# Power_CH341A.net
KiCad netlist of a schematic drawn in Altium Designer
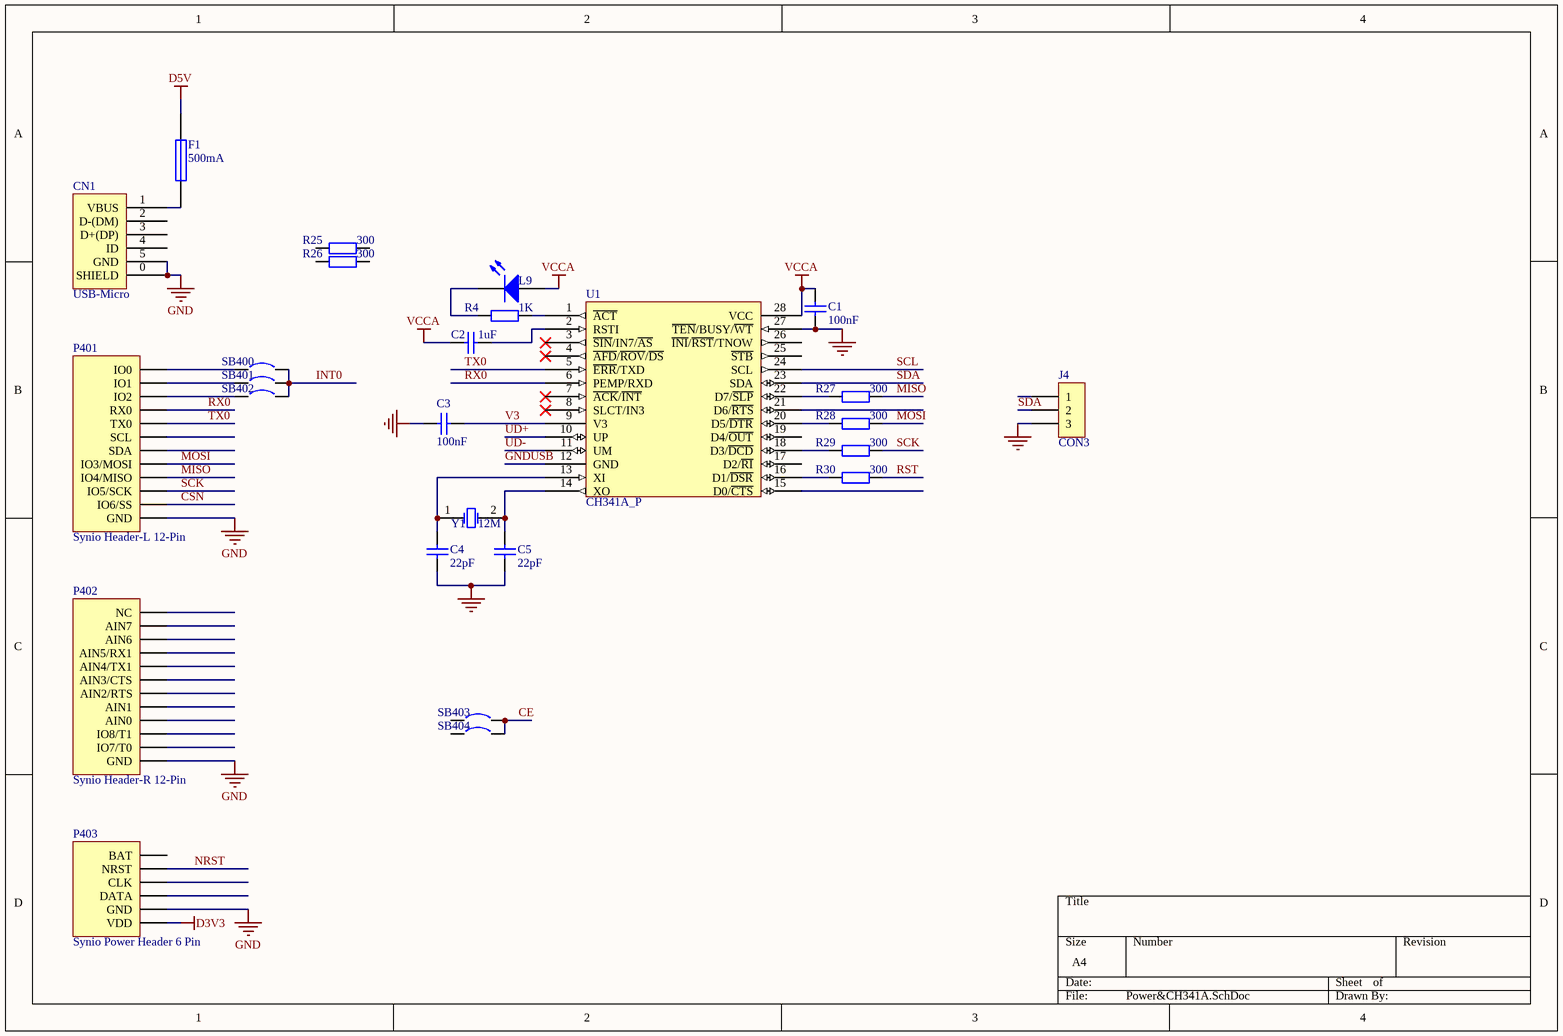
[diagram p0: Power&CH341A.SchDoc]

(export (version "E")
  (design (tool "Eeschema 10.0.6"))
  (components
    (comp (ref "C1")
      (value "100nF")
      (footprint "C0603L")
      (description "Capacitor")
      (fields (field (name "Comment") "Cap") (field (name "PUBLISHER") "Altium Limited"))
      (libsource (lib "Miscellaneous Devices") (part "Cap"))
    )
    (comp (ref "C2")
      (value "1uF")
      (footprint "C0603L")
      (description "Capacitor")
      (fields (field (name "Comment") "Cap") (field (name "PUBLISHER") "Altium Limited"))
      (libsource (lib "Miscellaneous Devices") (part "Cap"))
    )
    (comp (ref "C3")
      (value "100nF")
      (footprint "C0603L")
      (description "Capacitor")
      (fields (field (name "Comment") "Cap") (field (name "PUBLISHER") "Altium Limited"))
      (libsource (lib "Miscellaneous Devices") (part "Cap"))
    )
    (comp (ref "C4")
      (value "22pF")
      (footprint "C0603L")
      (description "Capacitor")
      (fields (field (name "Comment") "Cap") (field (name "PUBLISHER") "Altium Limited"))
      (libsource (lib "Miscellaneous Devices") (part "Cap"))
    )
    (comp (ref "C5")
      (value "22pF")
      (footprint "C0603L")
      (description "Capacitor")
      (fields (field (name "Comment") "Cap") (field (name "PUBLISHER") "Altium Limited"))
      (libsource (lib "Miscellaneous Devices") (part "Cap"))
    )
    (comp (ref "CN1")
      (value "USB-Micro")
      (footprint "USB-MICRO-Female-Lite")
      (libsource (lib "Connector") (part "USB-Micro"))
    )
    (comp (ref "F1")
      (value "500mA")
      (footprint "0805")
      (description "Fuse")
      (fields (field (name "PUBLISHER") "Altium Limited"))
      (libsource (lib "Studio") (part "Fuse 1"))
    )
    (comp (ref "J4")
      (value "CON3")
      (footprint "HDR1X3")
      (description "CON 3-Pin")
      (fields (field (name "PUBLISHER") "Altium Limited"))
      (libsource (lib "CT107D_SUDA") (part "CON3"))
    )
    (comp (ref "L9")
      (value "LED")
      (footprint "0603pn")
      (description "Typical RED, GREEN, YELLOW, AMBER GaAs LED")
      (fields (field (name "PUBLISHER") "Altium Limited"))
      (libsource (lib "CT107D_SUDA") (part "LED"))
    )
    (comp (ref "P401")
      (value "Synio Header-L 12-Pin")
      (footprint "HDR1X12-L/2.54MM")
      (description "Synio Header-L, 12-Pin")
      (fields (field (name "PUBLISHER") "Altium Limited"))
      (libsource (lib "Connector") (part "Synio Header-L 12-Pin"))
    )
    (comp (ref "P402")
      (value "Synio Header-R 12-Pin")
      (footprint "HDR1X12-L/2.54MM")
      (description "Synio Header-R, 12-Pin")
      (fields (field (name "PUBLISHER") "Altium Limited"))
      (libsource (lib "Connector") (part "Synio Header-R 12-Pin"))
    )
    (comp (ref "P403")
      (value "Synio Power Header 6 Pin")
      (footprint "HDR1X6-L/2.54MM")
      (libsource (lib "Connector") (part "Synio Power Header 6 Pin"))
    )
    (comp (ref "R4")
      (value "1K")
      (footprint "R0603")
      (description "Resistor")
      (fields (field (name "Comment") "Res") (field (name "PUBLISHER") "Altium Limited"))
      (libsource (lib "CT107D_SUDA") (part "Res"))
    )
    (comp (ref "R25")
      (value "300")
      (footprint "R0603")
      (description "Resistor")
      (fields (field (name "Comment") "Res") (field (name "PUBLISHER") "Altium Limited"))
      (libsource (lib "CT107D_SUDA") (part "Res"))
    )
    (comp (ref "R26")
      (value "300")
      (footprint "R0603")
      (description "Resistor")
      (fields (field (name "Comment") "Res") (field (name "PUBLISHER") "Altium Limited"))
      (libsource (lib "CT107D_SUDA") (part "Res"))
    )
    (comp (ref "R27")
      (value "300")
      (footprint "R0603")
      (description "Resistor")
      (fields (field (name "Comment") "Res") (field (name "PUBLISHER") "Altium Limited"))
      (libsource (lib "CT107D_SUDA") (part "Res"))
    )
    (comp (ref "R28")
      (value "300")
      (footprint "R0603")
      (description "Resistor")
      (fields (field (name "Comment") "Res") (field (name "PUBLISHER") "Altium Limited"))
      (libsource (lib "CT107D_SUDA") (part "Res"))
    )
    (comp (ref "R29")
      (value "300")
      (footprint "R0603")
      (description "Resistor")
      (fields (field (name "Comment") "Res") (field (name "PUBLISHER") "Altium Limited"))
      (libsource (lib "CT107D_SUDA") (part "Res"))
    )
    (comp (ref "R30")
      (value "300")
      (footprint "R0603")
      (description "Resistor")
      (fields (field (name "Comment") "Res") (field (name "PUBLISHER") "Altium Limited"))
      (libsource (lib "CT107D_SUDA") (part "Res"))
    )
    (comp (ref "SB400")
      (value "Circuit Breaker")
      (footprint "JP2_SMD")
      (fields (field (name "PUBLISHER") "Altium Limited"))
      (libsource (lib "Misc") (part "Circuit Breaker"))
    )
    (comp (ref "SB401")
      (value "Circuit Breaker")
      (footprint "JP2_SMD")
      (fields (field (name "PUBLISHER") "Altium Limited"))
      (libsource (lib "Misc") (part "Circuit Breaker"))
    )
    (comp (ref "SB402")
      (value "Circuit Breaker")
      (footprint "JP2_SMD")
      (fields (field (name "PUBLISHER") "Altium Limited"))
      (libsource (lib "Misc") (part "Circuit Breaker"))
    )
    (comp (ref "SB403")
      (value "Circuit Breaker")
      (footprint "JP2_SMD")
      (fields (field (name "PUBLISHER") "Altium Limited"))
      (libsource (lib "Misc") (part "Circuit Breaker"))
    )
    (comp (ref "SB404")
      (value "Circuit Breaker")
      (footprint "JP2_SMD")
      (fields (field (name "PUBLISHER") "Altium Limited"))
      (libsource (lib "Misc") (part "Circuit Breaker"))
    )
    (comp (ref "U1")
      (value "CH341A_P")
      (footprint "SO28_M")
      (description "USB bus convert chip")
      (libsource (lib "Logic") (part "CH341A"))
    )
    (comp (ref "Y1")
      (value "12M")
      (footprint "XTAL_49S")
      (description "Crystal Oscillator")
      (fields (field (name "Comment") "XTAL") (field (name "PUBLISHER") "Altium Limited"))
      (libsource (lib "CT107D_SUDA") (part "XTAL"))
    )
  )
  (nets
    (net (code "1") (name "/CE") (class "Default")
      (node (ref "SB403") (pin "2") (pinfunction "2_2") (pintype "passive"))
      (node (ref "SB404") (pin "2") (pinfunction "2_2") (pintype "passive"))
    )
    (net (code "2") (name "/CSN") (class "Default")
      (node (ref "P401") (pin "2") (pinfunction "IO6/SS_2") (pintype "passive"))
    )
    (net (code "3") (name "/INT0") (class "Default")
      (node (ref "SB400") (pin "2") (pinfunction "2_2") (pintype "passive"))
      (node (ref "SB401") (pin "2") (pinfunction "2_2") (pintype "passive"))
      (node (ref "SB402") (pin "2") (pinfunction "2_2") (pintype "passive"))
    )
    (net (code "4") (name "/MISO") (class "Default")
      (node (ref "P401") (pin "4") (pinfunction "IO4/MISO_4") (pintype "passive"))
      (node (ref "R27") (pin "2") (pinfunction "2_2") (pintype "passive"))
    )
    (net (code "5") (name "/MOSI") (class "Default")
      (node (ref "P401") (pin "5") (pinfunction "IO3/MOSI_5") (pintype "passive"))
      (node (ref "R28") (pin "2") (pinfunction "2_2") (pintype "passive"))
    )
    (net (code "6") (name "/NRST") (class "Default")
      (node (ref "P403") (pin "5") (pinfunction "NRST_5") (pintype "passive"))
    )
    (net (code "7") (name "/RST") (class "Default")
      (node (ref "R30") (pin "2") (pinfunction "2_2") (pintype "passive"))
    )
    (net (code "8") (name "/RX0") (class "Default")
      (node (ref "P401") (pin "9") (pinfunction "RX0_9") (pintype "passive"))
      (node (ref "U1") (pin "6") (pinfunction "PEMP/RXD_6") (pintype "input"))
    )
    (net (code "9") (name "/SCK") (class "Default")
      (node (ref "P401") (pin "3") (pinfunction "IO5/SCK_3") (pintype "passive"))
      (node (ref "R29") (pin "2") (pinfunction "2_2") (pintype "passive"))
    )
    (net (code "10") (name "/SCL") (class "Default")
      (node (ref "U1") (pin "24") (pinfunction "SCL_24") (pintype "output"))
    )
    (net (code "11") (name "/SDA") (class "Default")
      (node (ref "J4") (pin "2") (pinfunction "2_2") (pintype "passive"))
      (node (ref "U1") (pin "23") (pinfunction "SDA_23") (pintype "bidirectional"))
    )
    (net (code "12") (name "/TX0") (class "Default")
      (node (ref "P401") (pin "8") (pinfunction "TX0_8") (pintype "passive"))
      (node (ref "U1") (pin "5") (pinfunction "~{ERR}/TXD_5") (pintype "input"))
    )
    (net (code "13") (name "/UD+") (class "Default")
      (node (ref "U1") (pin "10") (pinfunction "UP_10") (pintype "bidirectional"))
    )
    (net (code "14") (name "/UD-") (class "Default")
      (node (ref "U1") (pin "11") (pinfunction "UM_11") (pintype "bidirectional"))
    )
    (net (code "15") (name "/V3") (class "Default")
      (node (ref "C3") (pin "1") (pinfunction "1_1") (pintype "passive"))
      (node (ref "U1") (pin "9") (pinfunction "V3_9") (pintype "power_in"))
    )
    (net (code "16") (name "D3V3") (class "Default")
      (node (ref "P403") (pin "1") (pinfunction "VDD_1") (pintype "passive"))
    )
    (net (code "17") (name "D5V") (class "Default")
      (node (ref "F1") (pin "1") (pinfunction "1_1") (pintype "passive"))
    )
    (net (code "18") (name "GND") (class "Default")
      (node (ref "CN1") (pin "0") (pinfunction "SHIELD_0") (pintype "passive"))
      (node (ref "CN1") (pin "5") (pinfunction "GND_5") (pintype "passive"))
      (node (ref "P401") (pin "1") (pinfunction "GND_1") (pintype "passive"))
      (node (ref "P402") (pin "1") (pinfunction "GND_1") (pintype "passive"))
      (node (ref "P403") (pin "2") (pinfunction "GND_2") (pintype "passive"))
    )
    (net (code "19") (name "GNDUSB") (class "Default")
      (node (ref "C1") (pin "1") (pinfunction "1_1") (pintype "passive"))
      (node (ref "C3") (pin "2") (pinfunction "2_2") (pintype "passive"))
      (node (ref "C4") (pin "1") (pinfunction "1_1") (pintype "passive"))
      (node (ref "C5") (pin "1") (pinfunction "1_1") (pintype "passive"))
      (node (ref "J4") (pin "3") (pinfunction "3_3") (pintype "passive"))
      (node (ref "U1") (pin "12") (pinfunction "GND_12") (pintype "power_in"))
      (node (ref "U1") (pin "27") (pinfunction "~{TEN}/BUSY/~{WT}_27") (pintype "input"))
    )
    (net (code "20") (name "Net-(CN1-VBUS)") (class "Default")
      (node (ref "CN1") (pin "1") (pinfunction "VBUS_1") (pintype "passive"))
      (node (ref "F1") (pin "2") (pinfunction "2_2") (pintype "passive"))
    )
    (net (code "21") (name "Net-(L9-K)") (class "Default")
      (node (ref "L9") (pin "2") (pinfunction "K_2") (pintype "passive"))
      (node (ref "R4") (pin "1") (pinfunction "1_1") (pintype "passive"))
    )
    (net (code "22") (name "Net-(P401-IO0)") (class "Default")
      (node (ref "P401") (pin "12") (pinfunction "IO0_12") (pintype "passive"))
      (node (ref "SB400") (pin "1") (pinfunction "1_1") (pintype "passive"))
    )
    (net (code "23") (name "Net-(P401-IO1)") (class "Default")
      (node (ref "P401") (pin "11") (pinfunction "IO1_11") (pintype "passive"))
      (node (ref "SB401") (pin "1") (pinfunction "1_1") (pintype "passive"))
    )
    (net (code "24") (name "Net-(P401-IO2)") (class "Default")
      (node (ref "P401") (pin "10") (pinfunction "IO2_10") (pintype "passive"))
      (node (ref "SB402") (pin "1") (pinfunction "1_1") (pintype "passive"))
    )
    (net (code "25") (name "Net-(U1-D1{slash}~{DSR})") (class "Default")
      (node (ref "R30") (pin "1") (pinfunction "1_1") (pintype "passive"))
      (node (ref "U1") (pin "16") (pinfunction "D1/~{DSR}_16") (pintype "bidirectional"))
    )
    (net (code "26") (name "Net-(U1-D3{slash}~{DCD})") (class "Default")
      (node (ref "R29") (pin "1") (pinfunction "1_1") (pintype "passive"))
      (node (ref "U1") (pin "18") (pinfunction "D3/~{DCD}_18") (pintype "bidirectional"))
    )
    (net (code "27") (name "Net-(U1-D5{slash}~{DTR})") (class "Default")
      (node (ref "R28") (pin "1") (pinfunction "1_1") (pintype "passive"))
      (node (ref "U1") (pin "20") (pinfunction "D5/~{DTR}_20") (pintype "bidirectional"))
    )
    (net (code "28") (name "Net-(U1-D7{slash}~{SLP})") (class "Default")
      (node (ref "R27") (pin "1") (pinfunction "1_1") (pintype "passive"))
      (node (ref "U1") (pin "22") (pinfunction "D7/~{SLP}_22") (pintype "bidirectional"))
    )
    (net (code "29") (name "Net-(U1-RSTI)") (class "Default")
      (node (ref "C2") (pin "1") (pinfunction "1_1") (pintype "passive"))
      (node (ref "U1") (pin "2") (pinfunction "RSTI_2") (pintype "input"))
    )
    (net (code "30") (name "Net-(U1-XI)") (class "Default")
      (node (ref "C4") (pin "2") (pinfunction "2_2") (pintype "passive"))
      (node (ref "U1") (pin "13") (pinfunction "XI_13") (pintype "input"))
      (node (ref "Y1") (pin "1") (pinfunction "OSC1_1") (pintype "passive"))
    )
    (net (code "31") (name "Net-(U1-XO)") (class "Default")
      (node (ref "C5") (pin "2") (pinfunction "2_2") (pintype "passive"))
      (node (ref "U1") (pin "14") (pinfunction "XO_14") (pintype "output"))
      (node (ref "Y1") (pin "2") (pinfunction "OSC2_2") (pintype "passive"))
    )
    (net (code "32") (name "Net-(U1-~{ACT})") (class "Default")
      (node (ref "R4") (pin "2") (pinfunction "2_2") (pintype "passive"))
      (node (ref "U1") (pin "1") (pinfunction "~{ACT}_1") (pintype "output"))
    )
    (net (code "33") (name "VCCA") (class "Default")
      (node (ref "C1") (pin "2") (pinfunction "2_2") (pintype "passive"))
      (node (ref "C2") (pin "2") (pinfunction "2_2") (pintype "passive"))
      (node (ref "L9") (pin "1") (pinfunction "A_1") (pintype "passive"))
      (node (ref "U1") (pin "28") (pinfunction "VCC_28") (pintype "power_in"))
    )
    (net (code "34") (name "unconnected-(CN1-D+(DP)-Pad3)") (class "Default")
      (node (ref "CN1") (pin "3") (pinfunction "D+(DP)_3") (pintype "passive"))
    )
    (net (code "35") (name "unconnected-(CN1-D-(DM)-Pad2)") (class "Default")
      (node (ref "CN1") (pin "2") (pinfunction "D-(DM)_2") (pintype "passive"))
    )
    (net (code "36") (name "unconnected-(CN1-ID-Pad4)") (class "Default")
      (node (ref "CN1") (pin "4") (pinfunction "ID_4") (pintype "passive"))
    )
    (net (code "37") (name "unconnected-(J4-Pad1)") (class "Default")
      (node (ref "J4") (pin "1") (pinfunction "1_1") (pintype "passive"))
    )
    (net (code "38") (name "unconnected-(P401-SCL-Pad7)") (class "Default")
      (node (ref "P401") (pin "7") (pinfunction "SCL_7") (pintype "passive"))
    )
    (net (code "39") (name "unconnected-(P401-SDA-Pad6)") (class "Default")
      (node (ref "P401") (pin "6") (pinfunction "SDA_6") (pintype "passive"))
    )
    (net (code "40") (name "unconnected-(P402-AIN0-Pad4)") (class "Default")
      (node (ref "P402") (pin "4") (pinfunction "AIN0_4") (pintype "passive"))
    )
    (net (code "41") (name "unconnected-(P402-AIN1-Pad5)") (class "Default")
      (node (ref "P402") (pin "5") (pinfunction "AIN1_5") (pintype "passive"))
    )
    (net (code "42") (name "unconnected-(P402-AIN2{slash}RTS-Pad6)") (class "Default")
      (node (ref "P402") (pin "6") (pinfunction "AIN2/RTS_6") (pintype "passive"))
    )
    (net (code "43") (name "unconnected-(P402-AIN3{slash}CTS-Pad7)") (class "Default")
      (node (ref "P402") (pin "7") (pinfunction "AIN3/CTS_7") (pintype "passive"))
    )
    (net (code "44") (name "unconnected-(P402-AIN4{slash}TX1-Pad8)") (class "Default")
      (node (ref "P402") (pin "8") (pinfunction "AIN4/TX1_8") (pintype "passive"))
    )
    (net (code "45") (name "unconnected-(P402-AIN5{slash}RX1-Pad9)") (class "Default")
      (node (ref "P402") (pin "9") (pinfunction "AIN5/RX1_9") (pintype "passive"))
    )
    (net (code "46") (name "unconnected-(P402-AIN6-Pad10)") (class "Default")
      (node (ref "P402") (pin "10") (pinfunction "AIN6_10") (pintype "passive"))
    )
    (net (code "47") (name "unconnected-(P402-AIN7-Pad11)") (class "Default")
      (node (ref "P402") (pin "11") (pinfunction "AIN7_11") (pintype "passive"))
    )
    (net (code "48") (name "unconnected-(P402-IO7{slash}T0-Pad2)") (class "Default")
      (node (ref "P402") (pin "2") (pinfunction "IO7/T0_2") (pintype "passive"))
    )
    (net (code "49") (name "unconnected-(P402-IO8{slash}T1-Pad3)") (class "Default")
      (node (ref "P402") (pin "3") (pinfunction "IO8/T1_3") (pintype "passive"))
    )
    (net (code "50") (name "unconnected-(P402-NC-Pad12)") (class "Default")
      (node (ref "P402") (pin "12") (pinfunction "NC_12") (pintype "passive"))
    )
    (net (code "51") (name "unconnected-(P403-BAT-Pad6)") (class "Default")
      (node (ref "P403") (pin "6") (pinfunction "BAT_6") (pintype "passive"))
    )
    (net (code "52") (name "unconnected-(P403-CLK-Pad4)") (class "Default")
      (node (ref "P403") (pin "4") (pinfunction "CLK_4") (pintype "passive"))
    )
    (net (code "53") (name "unconnected-(P403-DATA-Pad3)") (class "Default")
      (node (ref "P403") (pin "3") (pinfunction "DATA_3") (pintype "passive"))
    )
    (net (code "54") (name "unconnected-(R25-Pad1)") (class "Default")
      (node (ref "R25") (pin "1") (pinfunction "1_1") (pintype "passive"))
    )
    (net (code "55") (name "unconnected-(R25-Pad2)") (class "Default")
      (node (ref "R25") (pin "2") (pinfunction "2_2") (pintype "passive"))
    )
    (net (code "56") (name "unconnected-(R26-Pad1)") (class "Default")
      (node (ref "R26") (pin "1") (pinfunction "1_1") (pintype "passive"))
    )
    (net (code "57") (name "unconnected-(R26-Pad2)") (class "Default")
      (node (ref "R26") (pin "2") (pinfunction "2_2") (pintype "passive"))
    )
    (net (code "58") (name "unconnected-(SB403-Pad1)") (class "Default")
      (node (ref "SB403") (pin "1") (pinfunction "1_1") (pintype "passive"))
    )
    (net (code "59") (name "unconnected-(SB404-Pad1)") (class "Default")
      (node (ref "SB404") (pin "1") (pinfunction "1_1") (pintype "passive"))
    )
    (net (code "60") (name "unconnected-(U1-D0{slash}~{CTS}-Pad15)") (class "Default")
      (node (ref "U1") (pin "15") (pinfunction "D0/~{CTS}_15") (pintype "bidirectional"))
    )
    (net (code "61") (name "unconnected-(U1-D2{slash}~{RI}-Pad17)") (class "Default")
      (node (ref "U1") (pin "17") (pinfunction "D2/~{RI}_17") (pintype "bidirectional"))
    )
    (net (code "62") (name "unconnected-(U1-D4{slash}~{OUT}-Pad19)") (class "Default")
      (node (ref "U1") (pin "19") (pinfunction "D4/~{OUT}_19") (pintype "bidirectional"))
    )
    (net (code "63") (name "unconnected-(U1-D6{slash}~{RTS}-Pad21)") (class "Default")
      (node (ref "U1") (pin "21") (pinfunction "D6/~{RTS}_21") (pintype "bidirectional"))
    )
    (net (code "64") (name "unconnected-(U1-SLCT{slash}IN3-Pad8)") (class "Default")
      (node (ref "U1") (pin "8") (pinfunction "SLCT/IN3_8") (pintype "input+no_connect"))
    )
    (net (code "65") (name "unconnected-(U1-~{ACK}{slash}~{INT}-Pad7)") (class "Default")
      (node (ref "U1") (pin "7") (pinfunction "~{ACK}/~{INT}_7") (pintype "input+no_connect"))
    )
    (net (code "66") (name "unconnected-(U1-~{AFD}{slash}~{ROV}{slash}~{DS}-Pad4)") (class "Default")
      (node (ref "U1") (pin "4") (pinfunction "~{AFD}/~{ROV}/~{DS}_4") (pintype "output+no_connect"))
    )
    (net (code "67") (name "unconnected-(U1-~{INI}{slash}~{RST}{slash}TNOW-Pad26)") (class "Default")
      (node (ref "U1") (pin "26") (pinfunction "~{INI}/~{RST}/TNOW_26") (pintype "output"))
    )
    (net (code "68") (name "unconnected-(U1-~{SIN}{slash}IN7{slash}~{AS}-Pad3)") (class "Default")
      (node (ref "U1") (pin "3") (pinfunction "~{SIN}/IN7/~{AS}_3") (pintype "output+no_connect"))
    )
    (net (code "69") (name "unconnected-(U1-~{STB}-Pad25)") (class "Default")
      (node (ref "U1") (pin "25") (pinfunction "~{STB}_25") (pintype "output"))
    )
  )
)
